# GSMPart.net
KiCad netlist of a schematic drawn in Altium Designer
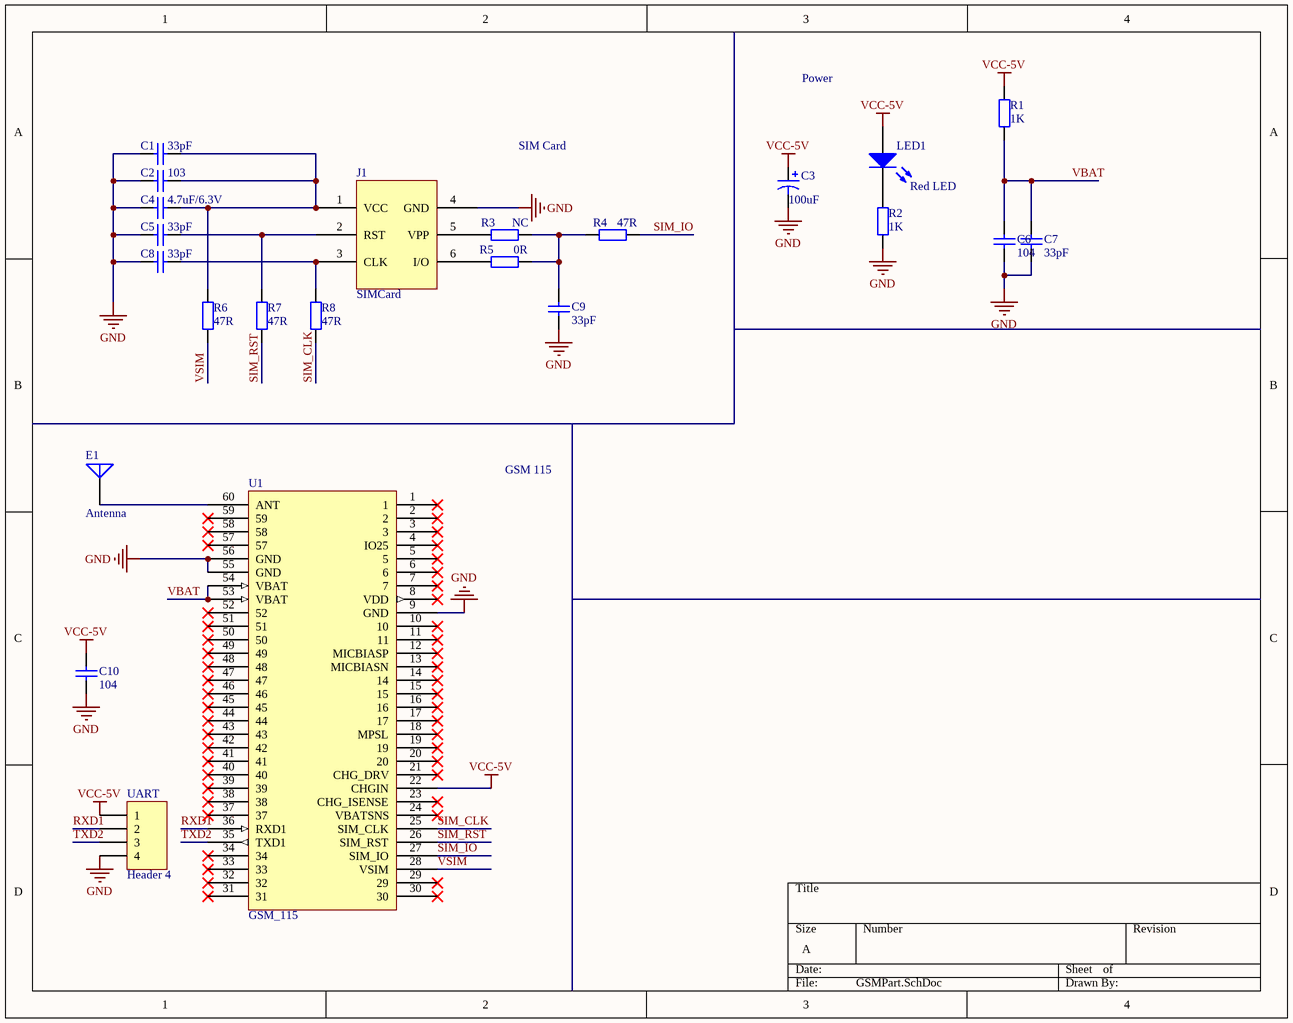
[diagram p0: GSMPart.SchDoc]

(export (version "E")
  (design (tool "Eeschema 10.0.6"))
  (components
    (comp (ref "C1")
      (value "33pF")
      (footprint "1608[0603]")
      (description "Capacitor")
      (fields (field (name "Comment") "Cap") (field (name "PUBLISHER") "Altium Limited"))
      (libsource (lib "common") (part "Cap"))
    )
    (comp (ref "C2")
      (value "103")
      (footprint "1608[0603]")
      (description "Capacitor")
      (fields (field (name "Comment") "Cap") (field (name "PUBLISHER") "Altium Limited"))
      (libsource (lib "common") (part "Cap"))
    )
    (comp (ref "C3")
      (value "100uF")
      (footprint "2012[0805] - POL")
      (description "Polarized Capacitor (Axial)")
      (fields (field (name "Comment") "CAP POL") (field (name "PUBLISHER") "Altium Limited"))
      (libsource (lib "common") (part "CAP POL"))
    )
    (comp (ref "C4")
      (value "4.7uF/6.3V")
      (footprint "1608[0603]")
      (description "Capacitor")
      (fields (field (name "Comment") "Cap") (field (name "PUBLISHER") "Altium Limited"))
      (libsource (lib "common") (part "Cap"))
    )
    (comp (ref "C5")
      (value "33pF")
      (footprint "1608[0603]")
      (description "Capacitor")
      (fields (field (name "Comment") "Cap") (field (name "PUBLISHER") "Altium Limited"))
      (libsource (lib "common") (part "Cap"))
    )
    (comp (ref "C6")
      (value "104")
      (footprint "1608[0603]")
      (description "Capacitor")
      (fields (field (name "Comment") "Cap") (field (name "PUBLISHER") "Altium Limited"))
      (libsource (lib "common") (part "Cap"))
    )
    (comp (ref "C7")
      (value "33pF")
      (footprint "1608[0603]")
      (description "Capacitor")
      (fields (field (name "Comment") "Cap") (field (name "PUBLISHER") "Altium Limited"))
      (libsource (lib "common") (part "Cap"))
    )
    (comp (ref "C8")
      (value "33pF")
      (footprint "1608[0603]")
      (description "Capacitor")
      (fields (field (name "Comment") "Cap") (field (name "PUBLISHER") "Altium Limited"))
      (libsource (lib "common") (part "Cap"))
    )
    (comp (ref "C9")
      (value "33pF")
      (footprint "1608[0603]")
      (description "Capacitor")
      (fields (field (name "Comment") "Cap") (field (name "PUBLISHER") "Altium Limited"))
      (libsource (lib "common") (part "Cap"))
    )
    (comp (ref "C10")
      (value "104")
      (footprint "1608[0603]")
      (description "Capacitor")
      (fields (field (name "Comment") "Cap") (field (name "PUBLISHER") "Altium Limited"))
      (libsource (lib "common") (part "Cap"))
    )
    (comp (ref "E1")
      (value "Antenna")
      (footprint "PIN1")
      (description "Generic Antenna")
      (fields (field (name "PUBLISHER") "Altium Limited"))
      (libsource (lib "Miscellaneous Devices") (part "Antenna"))
    )
    (comp (ref "J1")
      (value "SIMCard")
      (footprint "PCB_SIM")
      (description "Sim Card")
      (libsource (lib "*") (part "SIMCard"))
    )
    (comp (ref "LED1")
      (value "Red LED")
      (footprint "1608[0603] - POL")
      (libsource (lib "common") (part "LED"))
    )
    (comp (ref "R1")
      (value "1K")
      (footprint "1608[0603]")
      (description "Resistor")
      (fields (field (name "Comment") "RES") (field (name "PUBLISHER") "Altium Limited"))
      (libsource (lib "") (part "RES_1"))
    )
    (comp (ref "R2")
      (value "1K")
      (footprint "1608[0603]")
      (description "Resistor")
      (fields (field (name "Comment") "RES") (field (name "PUBLISHER") "Altium Limited"))
      (libsource (lib "") (part "RES_1"))
    )
    (comp (ref "R3")
      (value "NC")
      (footprint "1608[0603]")
      (description "Resistor")
      (fields (field (name "Comment") "RES") (field (name "PUBLISHER") "Altium Limited"))
      (libsource (lib "common") (part "RES"))
    )
    (comp (ref "R4")
      (value "47R")
      (footprint "1608[0603]")
      (description "Resistor")
      (fields (field (name "Comment") "RES") (field (name "PUBLISHER") "Altium Limited"))
      (libsource (lib "common") (part "RES"))
    )
    (comp (ref "R5")
      (value "0R")
      (footprint "1608[0603]")
      (description "Resistor")
      (fields (field (name "Comment") "RES") (field (name "PUBLISHER") "Altium Limited"))
      (libsource (lib "common") (part "RES"))
    )
    (comp (ref "R6")
      (value "47R")
      (footprint "1608[0603]")
      (description "Resistor")
      (fields (field (name "Comment") "RES") (field (name "PUBLISHER") "Altium Limited"))
      (libsource (lib "") (part "RES_1"))
    )
    (comp (ref "R7")
      (value "47R")
      (footprint "1608[0603]")
      (description "Resistor")
      (fields (field (name "Comment") "RES") (field (name "PUBLISHER") "Altium Limited"))
      (libsource (lib "") (part "RES_1"))
    )
    (comp (ref "R8")
      (value "47R")
      (footprint "1608[0603]")
      (description "Resistor")
      (fields (field (name "Comment") "RES") (field (name "PUBLISHER") "Altium Limited"))
      (libsource (lib "") (part "RES_1"))
    )
    (comp (ref "U1") (value "GSM_115") (libsource (lib "GSM") (part "GSM115")))
    (comp (ref "UART")
      (value "Header 4")
      (footprint "HDR1X4")
      (description "Header, 4-Pin")
      (fields (field (name "PUBLISHER") "Altium Limited"))
      (libsource (lib "Miscellaneous Connectors") (part "Header 4"))
    )
  )
  (nets
    (net (code "1") (name "/RXD1") (class "Default")
      (node (ref "U1") (pin "36") (pinfunction "RXD1_36") (pintype "input"))
      (node (ref "UART") (pin "2") (pinfunction "2_2") (pintype "passive"))
    )
    (net (code "2") (name "/SIM_CLK") (class "Default")
      (node (ref "R8") (pin "1") (pinfunction "1_1") (pintype "passive"))
      (node (ref "U1") (pin "25") (pinfunction "SIM_CLK_25") (pintype "passive"))
    )
    (net (code "3") (name "/SIM_IO") (class "Default")
      (node (ref "R4") (pin "2") (pinfunction "2_2") (pintype "passive"))
      (node (ref "U1") (pin "27") (pinfunction "SIM_IO_27") (pintype "passive"))
    )
    (net (code "4") (name "/SIM_RST") (class "Default")
      (node (ref "R7") (pin "1") (pinfunction "1_1") (pintype "passive"))
      (node (ref "U1") (pin "26") (pinfunction "SIM_RST_26") (pintype "passive"))
    )
    (net (code "5") (name "/TXD2") (class "Default")
      (node (ref "U1") (pin "35") (pinfunction "TXD1_35") (pintype "output"))
      (node (ref "UART") (pin "3") (pinfunction "3_3") (pintype "passive"))
    )
    (net (code "6") (name "/VBAT") (class "Default")
      (node (ref "C6") (pin "2") (pinfunction "2_2") (pintype "passive"))
      (node (ref "C7") (pin "2") (pinfunction "2_2") (pintype "passive"))
      (node (ref "R1") (pin "1") (pinfunction "1_1") (pintype "passive"))
      (node (ref "U1") (pin "53") (pinfunction "VBAT_53") (pintype "input"))
      (node (ref "U1") (pin "54") (pinfunction "VBAT_54") (pintype "input"))
    )
    (net (code "7") (name "/VSIM") (class "Default")
      (node (ref "R6") (pin "1") (pinfunction "1_1") (pintype "passive"))
      (node (ref "U1") (pin "28") (pinfunction "VSIM_28") (pintype "passive"))
    )
    (net (code "8") (name "GND") (class "Default")
      (node (ref "C1") (pin "1") (pinfunction "1_1") (pintype "passive"))
      (node (ref "C10") (pin "1") (pinfunction "1_1") (pintype "passive"))
      (node (ref "C2") (pin "1") (pinfunction "1_1") (pintype "passive"))
      (node (ref "C3") (pin "2") (pinfunction "2_2") (pintype "passive"))
      (node (ref "C4") (pin "1") (pinfunction "1_1") (pintype "passive"))
      (node (ref "C5") (pin "1") (pinfunction "1_1") (pintype "passive"))
      (node (ref "C6") (pin "1") (pinfunction "1_1") (pintype "passive"))
      (node (ref "C7") (pin "1") (pinfunction "1_1") (pintype "passive"))
      (node (ref "C8") (pin "1") (pinfunction "1_1") (pintype "passive"))
      (node (ref "C9") (pin "1") (pinfunction "1_1") (pintype "passive"))
      (node (ref "J1") (pin "4") (pinfunction "GND_4") (pintype "passive"))
      (node (ref "R2") (pin "1") (pinfunction "1_1") (pintype "passive"))
      (node (ref "U1") (pin "55") (pinfunction "GND_55") (pintype "passive"))
      (node (ref "U1") (pin "56") (pinfunction "GND_56") (pintype "passive"))
      (node (ref "U1") (pin "9") (pinfunction "GND_9") (pintype "passive"))
      (node (ref "UART") (pin "4") (pinfunction "4_4") (pintype "passive"))
    )
    (net (code "9") (name "Net-(C9-Pad2)") (class "Default")
      (node (ref "C9") (pin "2") (pinfunction "2_2") (pintype "passive"))
      (node (ref "R3") (pin "2") (pinfunction "2_2") (pintype "passive"))
      (node (ref "R4") (pin "1") (pinfunction "1_1") (pintype "passive"))
      (node (ref "R5") (pin "2") (pinfunction "2_2") (pintype "passive"))
    )
    (net (code "10") (name "Net-(E1-A)") (class "Default")
      (node (ref "E1") (pin "1") (pinfunction "A_1") (pintype "passive"))
      (node (ref "U1") (pin "60") (pinfunction "ANT_60") (pintype "passive"))
    )
    (net (code "11") (name "Net-(J1-CLK)") (class "Default")
      (node (ref "C8") (pin "2") (pinfunction "2_2") (pintype "passive"))
      (node (ref "J1") (pin "3") (pinfunction "CLK_3") (pintype "passive"))
      (node (ref "R8") (pin "2") (pinfunction "2_2") (pintype "passive"))
    )
    (net (code "12") (name "Net-(J1-I{slash}O)") (class "Default")
      (node (ref "J1") (pin "6") (pinfunction "I/O_6") (pintype "passive"))
      (node (ref "R5") (pin "1") (pinfunction "1_1") (pintype "passive"))
    )
    (net (code "13") (name "Net-(J1-RST)") (class "Default")
      (node (ref "C5") (pin "2") (pinfunction "2_2") (pintype "passive"))
      (node (ref "J1") (pin "2") (pinfunction "RST_2") (pintype "passive"))
      (node (ref "R7") (pin "2") (pinfunction "2_2") (pintype "passive"))
    )
    (net (code "14") (name "Net-(J1-VCC)") (class "Default")
      (node (ref "C1") (pin "2") (pinfunction "2_2") (pintype "passive"))
      (node (ref "C2") (pin "2") (pinfunction "2_2") (pintype "passive"))
      (node (ref "C4") (pin "2") (pinfunction "2_2") (pintype "passive"))
      (node (ref "J1") (pin "1") (pinfunction "VCC_1") (pintype "passive"))
      (node (ref "R6") (pin "2") (pinfunction "2_2") (pintype "passive"))
    )
    (net (code "15") (name "Net-(J1-VPP)") (class "Default")
      (node (ref "J1") (pin "5") (pinfunction "VPP_5") (pintype "passive"))
      (node (ref "R3") (pin "1") (pinfunction "1_1") (pintype "passive"))
    )
    (net (code "16") (name "Net-(LED1-K)") (class "Default")
      (node (ref "LED1") (pin "2") (pinfunction "K_2") (pintype "passive"))
      (node (ref "R2") (pin "2") (pinfunction "2_2") (pintype "passive"))
    )
    (net (code "17") (name "VCC-5V") (class "Default")
      (node (ref "C10") (pin "2") (pinfunction "2_2") (pintype "passive"))
      (node (ref "C3") (pin "1") (pinfunction "1_1") (pintype "passive"))
      (node (ref "LED1") (pin "1") (pinfunction "A_1") (pintype "passive"))
      (node (ref "R1") (pin "2") (pinfunction "2_2") (pintype "passive"))
      (node (ref "U1") (pin "22") (pinfunction "CHGIN_22") (pintype "passive"))
      (node (ref "UART") (pin "1") (pinfunction "1_1") (pintype "passive"))
    )
    (net (code "18") (name "unconnected-(U1-CHG_DRV-Pad21)") (class "Default")
      (node (ref "U1") (pin "21") (pinfunction "CHG_DRV_21") (pintype "passive+no_connect"))
    )
    (net (code "19") (name "unconnected-(U1-CHG_ISENSE-Pad23)") (class "Default")
      (node (ref "U1") (pin "23") (pinfunction "CHG_ISENSE_23") (pintype "passive+no_connect"))
    )
    (net (code "20") (name "unconnected-(U1-IO25-Pad4)") (class "Default")
      (node (ref "U1") (pin "4") (pinfunction "IO25_4") (pintype "passive+no_connect"))
    )
    (net (code "21") (name "unconnected-(U1-MICBIASN-Pad13)") (class "Default")
      (node (ref "U1") (pin "13") (pinfunction "MICBIASN_13") (pintype "passive+no_connect"))
    )
    (net (code "22") (name "unconnected-(U1-MICBIASP-Pad12)") (class "Default")
      (node (ref "U1") (pin "12") (pinfunction "MICBIASP_12") (pintype "passive+no_connect"))
    )
    (net (code "23") (name "unconnected-(U1-MPSL-Pad18)") (class "Default")
      (node (ref "U1") (pin "18") (pinfunction "MPSL_18") (pintype "passive+no_connect"))
    )
    (net (code "24") (name "unconnected-(U1-Pad1)") (class "Default")
      (node (ref "U1") (pin "1") (pinfunction "1_1") (pintype "passive+no_connect"))
    )
    (net (code "25") (name "unconnected-(U1-Pad2)") (class "Default")
      (node (ref "U1") (pin "2") (pinfunction "2_2") (pintype "passive+no_connect"))
    )
    (net (code "26") (name "unconnected-(U1-Pad3)") (class "Default")
      (node (ref "U1") (pin "3") (pinfunction "3_3") (pintype "passive+no_connect"))
    )
    (net (code "27") (name "unconnected-(U1-Pad5)") (class "Default")
      (node (ref "U1") (pin "5") (pinfunction "5_5") (pintype "passive+no_connect"))
    )
    (net (code "28") (name "unconnected-(U1-Pad6)") (class "Default")
      (node (ref "U1") (pin "6") (pinfunction "6_6") (pintype "passive+no_connect"))
    )
    (net (code "29") (name "unconnected-(U1-Pad7)") (class "Default")
      (node (ref "U1") (pin "7") (pinfunction "7_7") (pintype "passive+no_connect"))
    )
    (net (code "30") (name "unconnected-(U1-Pad10)") (class "Default")
      (node (ref "U1") (pin "10") (pinfunction "10_10") (pintype "passive+no_connect"))
    )
    (net (code "31") (name "unconnected-(U1-Pad11)") (class "Default")
      (node (ref "U1") (pin "11") (pinfunction "11_11") (pintype "passive+no_connect"))
    )
    (net (code "32") (name "unconnected-(U1-Pad14)") (class "Default")
      (node (ref "U1") (pin "14") (pinfunction "14_14") (pintype "passive+no_connect"))
    )
    (net (code "33") (name "unconnected-(U1-Pad15)") (class "Default")
      (node (ref "U1") (pin "15") (pinfunction "15_15") (pintype "passive+no_connect"))
    )
    (net (code "34") (name "unconnected-(U1-Pad16)") (class "Default")
      (node (ref "U1") (pin "16") (pinfunction "16_16") (pintype "passive+no_connect"))
    )
    (net (code "35") (name "unconnected-(U1-Pad17)") (class "Default")
      (node (ref "U1") (pin "17") (pinfunction "17_17") (pintype "passive+no_connect"))
    )
    (net (code "36") (name "unconnected-(U1-Pad19)") (class "Default")
      (node (ref "U1") (pin "19") (pinfunction "19_19") (pintype "passive+no_connect"))
    )
    (net (code "37") (name "unconnected-(U1-Pad20)") (class "Default")
      (node (ref "U1") (pin "20") (pinfunction "20_20") (pintype "passive+no_connect"))
    )
    (net (code "38") (name "unconnected-(U1-Pad29)") (class "Default")
      (node (ref "U1") (pin "29") (pinfunction "29_29") (pintype "passive+no_connect"))
    )
    (net (code "39") (name "unconnected-(U1-Pad30)") (class "Default")
      (node (ref "U1") (pin "30") (pinfunction "30_30") (pintype "passive+no_connect"))
    )
    (net (code "40") (name "unconnected-(U1-Pad31)") (class "Default")
      (node (ref "U1") (pin "31") (pinfunction "31_31") (pintype "passive+no_connect"))
    )
    (net (code "41") (name "unconnected-(U1-Pad32)") (class "Default")
      (node (ref "U1") (pin "32") (pinfunction "32_32") (pintype "passive+no_connect"))
    )
    (net (code "42") (name "unconnected-(U1-Pad33)") (class "Default")
      (node (ref "U1") (pin "33") (pinfunction "33_33") (pintype "passive+no_connect"))
    )
    (net (code "43") (name "unconnected-(U1-Pad34)") (class "Default")
      (node (ref "U1") (pin "34") (pinfunction "34_34") (pintype "passive+no_connect"))
    )
    (net (code "44") (name "unconnected-(U1-Pad37)") (class "Default")
      (node (ref "U1") (pin "37") (pinfunction "37_37") (pintype "passive+no_connect"))
    )
    (net (code "45") (name "unconnected-(U1-Pad38)") (class "Default")
      (node (ref "U1") (pin "38") (pinfunction "38_38") (pintype "passive+no_connect"))
    )
    (net (code "46") (name "unconnected-(U1-Pad39)") (class "Default")
      (node (ref "U1") (pin "39") (pinfunction "39_39") (pintype "passive+no_connect"))
    )
    (net (code "47") (name "unconnected-(U1-Pad40)") (class "Default")
      (node (ref "U1") (pin "40") (pinfunction "40_40") (pintype "passive+no_connect"))
    )
    (net (code "48") (name "unconnected-(U1-Pad41)") (class "Default")
      (node (ref "U1") (pin "41") (pinfunction "41_41") (pintype "passive+no_connect"))
    )
    (net (code "49") (name "unconnected-(U1-Pad42)") (class "Default")
      (node (ref "U1") (pin "42") (pinfunction "42_42") (pintype "passive+no_connect"))
    )
    (net (code "50") (name "unconnected-(U1-Pad43)") (class "Default")
      (node (ref "U1") (pin "43") (pinfunction "43_43") (pintype "passive+no_connect"))
    )
    (net (code "51") (name "unconnected-(U1-Pad44)") (class "Default")
      (node (ref "U1") (pin "44") (pinfunction "44_44") (pintype "passive+no_connect"))
    )
    (net (code "52") (name "unconnected-(U1-Pad45)") (class "Default")
      (node (ref "U1") (pin "45") (pinfunction "45_45") (pintype "passive+no_connect"))
    )
    (net (code "53") (name "unconnected-(U1-Pad46)") (class "Default")
      (node (ref "U1") (pin "46") (pinfunction "46_46") (pintype "passive+no_connect"))
    )
    (net (code "54") (name "unconnected-(U1-Pad47)") (class "Default")
      (node (ref "U1") (pin "47") (pinfunction "47_47") (pintype "passive+no_connect"))
    )
    (net (code "55") (name "unconnected-(U1-Pad48)") (class "Default")
      (node (ref "U1") (pin "48") (pinfunction "48_48") (pintype "passive+no_connect"))
    )
    (net (code "56") (name "unconnected-(U1-Pad49)") (class "Default")
      (node (ref "U1") (pin "49") (pinfunction "49_49") (pintype "passive+no_connect"))
    )
    (net (code "57") (name "unconnected-(U1-Pad50)") (class "Default")
      (node (ref "U1") (pin "50") (pinfunction "50_50") (pintype "passive+no_connect"))
    )
    (net (code "58") (name "unconnected-(U1-Pad51)") (class "Default")
      (node (ref "U1") (pin "51") (pinfunction "51_51") (pintype "passive+no_connect"))
    )
    (net (code "59") (name "unconnected-(U1-Pad52)") (class "Default")
      (node (ref "U1") (pin "52") (pinfunction "52_52") (pintype "passive+no_connect"))
    )
    (net (code "60") (name "unconnected-(U1-Pad57)") (class "Default")
      (node (ref "U1") (pin "57") (pinfunction "57_57") (pintype "passive+no_connect"))
    )
    (net (code "61") (name "unconnected-(U1-Pad58)") (class "Default")
      (node (ref "U1") (pin "58") (pinfunction "58_58") (pintype "passive+no_connect"))
    )
    (net (code "62") (name "unconnected-(U1-Pad59)") (class "Default")
      (node (ref "U1") (pin "59") (pinfunction "59_59") (pintype "passive+no_connect"))
    )
    (net (code "63") (name "unconnected-(U1-VBATSNS-Pad24)") (class "Default")
      (node (ref "U1") (pin "24") (pinfunction "VBATSNS_24") (pintype "passive+no_connect"))
    )
    (net (code "64") (name "unconnected-(U1-VDD-Pad8)") (class "Default")
      (node (ref "U1") (pin "8") (pinfunction "VDD_8") (pintype "output+no_connect"))
    )
  )
)
